# PIEFoundry_16-channel_EIB.net
KiCad netlist of a schematic drawn in EAGLE
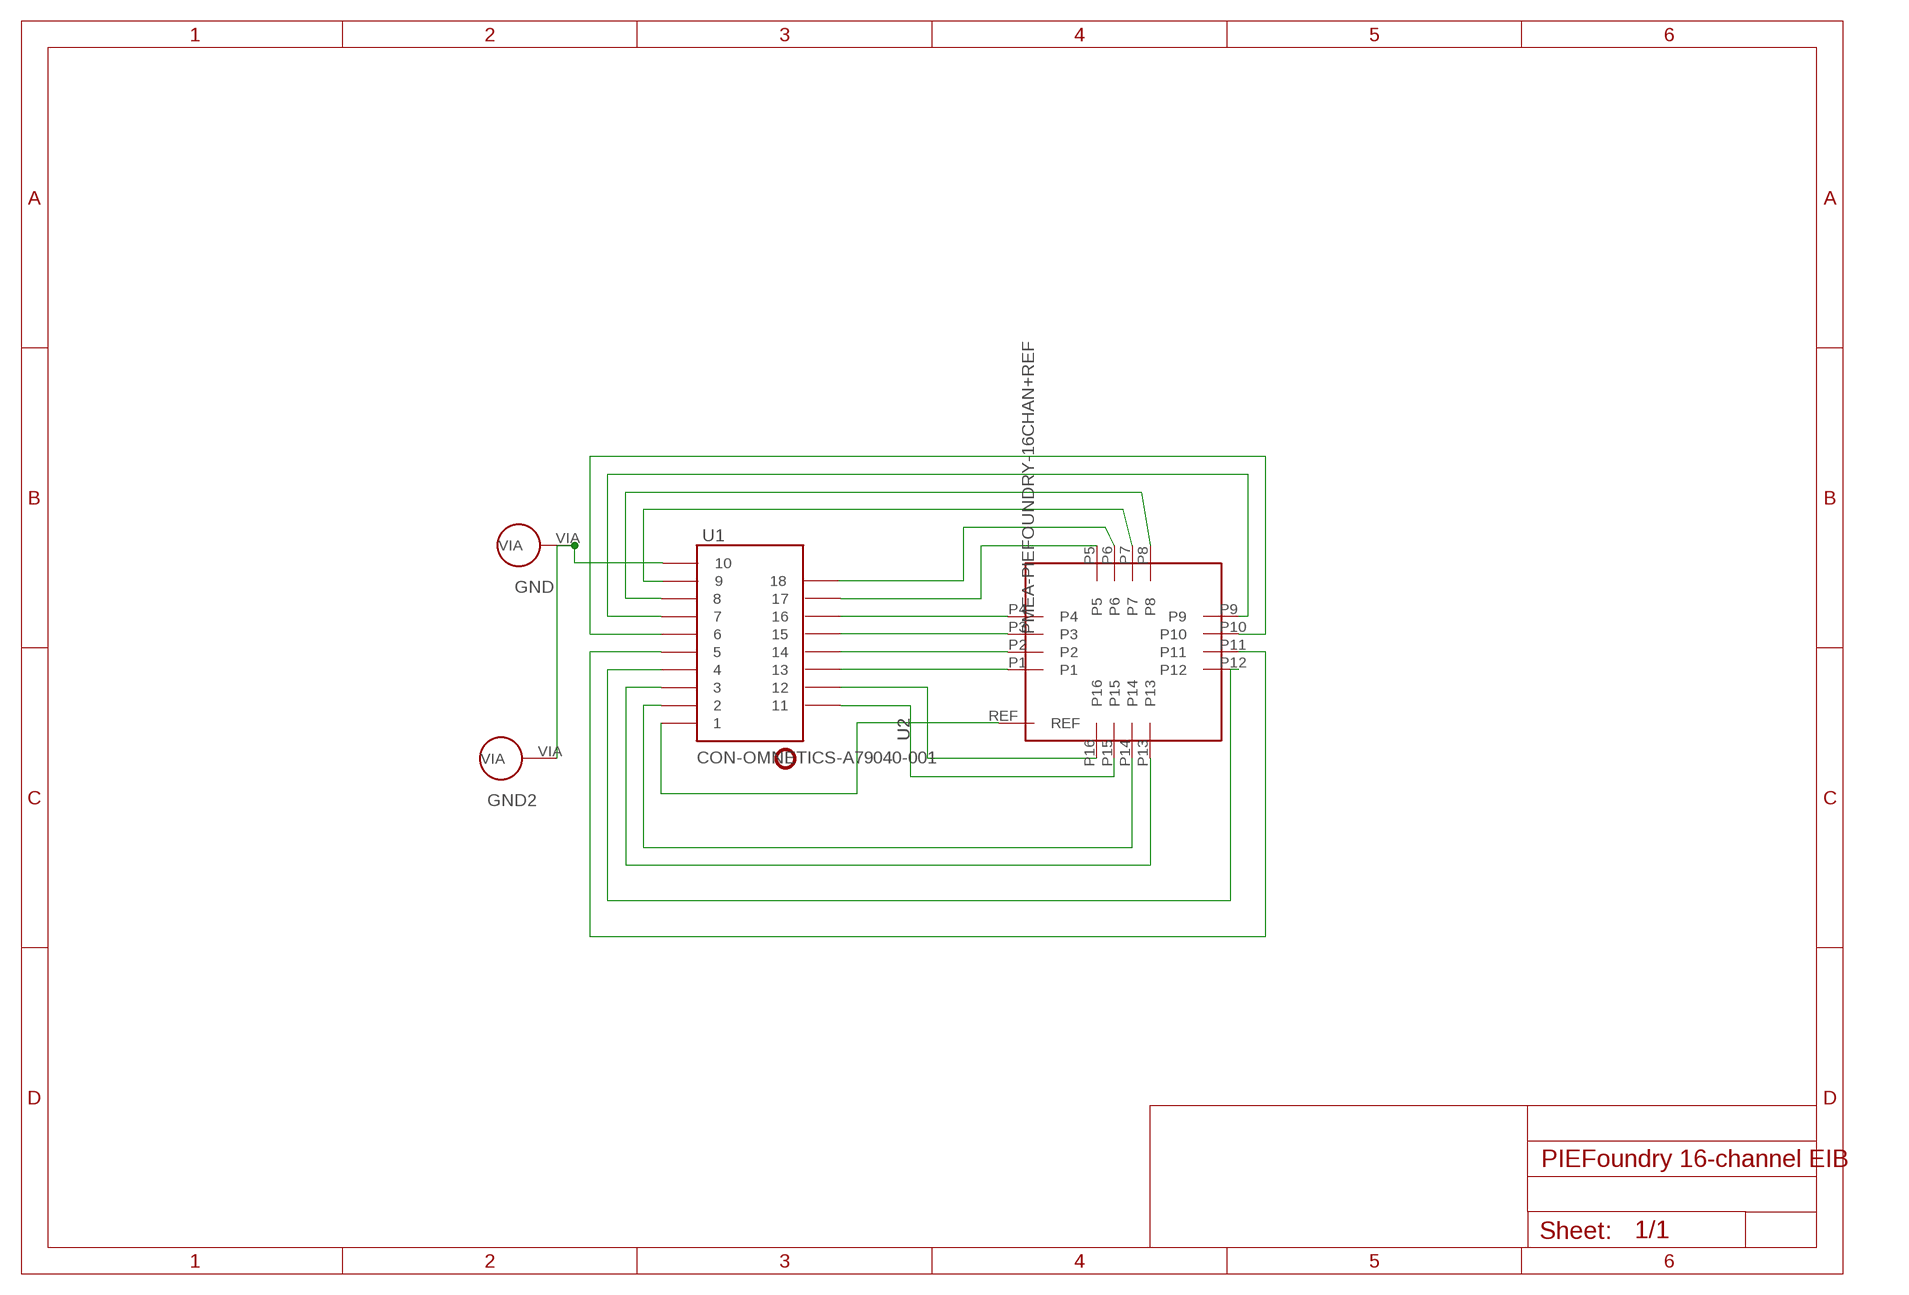
[diagram p0: schematic, sheet 1]

(export (version "E")
  (design (tool "Eeschema 10.0.6"))
  (components
    (comp (ref "GND")
      (value "SOLDER_VIA_500_UM")
      (footprint "eagle-import:SOLDER_VIA_500_UM")
      (libsource (lib "eagle-import") (part "SOLDER_VIA_500_UM"))
    )
    (comp (ref "GND2")
      (value "SOLDER_VIA_500_UM")
      (footprint "eagle-import:SOLDER_VIA_500_UM")
      (libsource (lib "eagle-import") (part "SOLDER_VIA_500_UM"))
    )
    (comp (ref "U1")
      (value "CON-OMNETICS-A79040-001")
      (footprint "eagle-import:CON-OMNETICS-A79040-001")
      (libsource (lib "eagle-import") (part "CON-OMNETICS-A79040-001"))
    )
    (comp (ref "U2")
      (value "PMEA-PIEFOUNDRY-16CHAN+REF")
      (footprint "eagle-import:PMEA-PIEFOUNDRY-16CHAN+REF")
      (libsource (lib "eagle-import") (part "PMEA-PIEFOUNDRY-16CHAN+REF"))
    )
  )
  (nets
    (net (code "1") (name "Net-(GND-PadVIA)") (class "Default")
      (node (ref "GND") (pin "VIA") (pinfunction "VIA_VIA") (pintype "bidirectional"))
      (node (ref "GND2") (pin "VIA") (pinfunction "VIA_VIA") (pintype "bidirectional"))
      (node (ref "U1") (pin "10") (pinfunction "10_10") (pintype "bidirectional"))
    )
    (net (code "2") (name "Net-(U1-Pad1)") (class "Default")
      (node (ref "U1") (pin "1") (pinfunction "1_1") (pintype "bidirectional"))
      (node (ref "U2") (pin "REF") (pinfunction "REF_REF") (pintype "bidirectional"))
    )
    (net (code "3") (name "Net-(U1-Pad2)") (class "Default")
      (node (ref "U1") (pin "2") (pinfunction "2_2") (pintype "bidirectional"))
      (node (ref "U2") (pin "P14") (pinfunction "P14_P14") (pintype "bidirectional"))
    )
    (net (code "4") (name "Net-(U1-Pad3)") (class "Default")
      (node (ref "U1") (pin "3") (pinfunction "3_3") (pintype "bidirectional"))
      (node (ref "U2") (pin "P13") (pinfunction "P13_P13") (pintype "bidirectional"))
    )
    (net (code "5") (name "Net-(U1-Pad4)") (class "Default")
      (node (ref "U1") (pin "4") (pinfunction "4_4") (pintype "bidirectional"))
      (node (ref "U2") (pin "P12") (pinfunction "P12_P12") (pintype "bidirectional"))
    )
    (net (code "6") (name "Net-(U1-Pad5)") (class "Default")
      (node (ref "U1") (pin "5") (pinfunction "5_5") (pintype "bidirectional"))
      (node (ref "U2") (pin "P11") (pinfunction "P11_P11") (pintype "bidirectional"))
    )
    (net (code "7") (name "Net-(U1-Pad6)") (class "Default")
      (node (ref "U1") (pin "6") (pinfunction "6_6") (pintype "bidirectional"))
      (node (ref "U2") (pin "P10") (pinfunction "P10_P10") (pintype "bidirectional"))
    )
    (net (code "8") (name "Net-(U1-Pad7)") (class "Default")
      (node (ref "U1") (pin "7") (pinfunction "7_7") (pintype "bidirectional"))
      (node (ref "U2") (pin "P9") (pinfunction "P9_P9") (pintype "bidirectional"))
    )
    (net (code "9") (name "Net-(U1-Pad8)") (class "Default")
      (node (ref "U1") (pin "8") (pinfunction "8_8") (pintype "bidirectional"))
      (node (ref "U2") (pin "P8") (pinfunction "P8_P8") (pintype "bidirectional"))
    )
    (net (code "10") (name "Net-(U1-Pad9)") (class "Default")
      (node (ref "U1") (pin "9") (pinfunction "9_9") (pintype "bidirectional"))
      (node (ref "U2") (pin "P7") (pinfunction "P7_P7") (pintype "bidirectional"))
    )
    (net (code "11") (name "Net-(U1-Pad11)") (class "Default")
      (node (ref "U1") (pin "11") (pinfunction "11_11") (pintype "bidirectional"))
      (node (ref "U2") (pin "P15") (pinfunction "P15_P15") (pintype "bidirectional"))
    )
    (net (code "12") (name "Net-(U1-Pad12)") (class "Default")
      (node (ref "U1") (pin "12") (pinfunction "12_12") (pintype "bidirectional"))
      (node (ref "U2") (pin "P16") (pinfunction "P16_P16") (pintype "bidirectional"))
    )
    (net (code "13") (name "Net-(U1-Pad13)") (class "Default")
      (node (ref "U1") (pin "13") (pinfunction "13_13") (pintype "bidirectional"))
      (node (ref "U2") (pin "P1") (pinfunction "P1_P1") (pintype "bidirectional"))
    )
    (net (code "14") (name "Net-(U1-Pad14)") (class "Default")
      (node (ref "U1") (pin "14") (pinfunction "14_14") (pintype "bidirectional"))
      (node (ref "U2") (pin "P2") (pinfunction "P2_P2") (pintype "bidirectional"))
    )
    (net (code "15") (name "Net-(U1-Pad15)") (class "Default")
      (node (ref "U1") (pin "15") (pinfunction "15_15") (pintype "bidirectional"))
      (node (ref "U2") (pin "P3") (pinfunction "P3_P3") (pintype "bidirectional"))
    )
    (net (code "16") (name "Net-(U1-Pad16)") (class "Default")
      (node (ref "U1") (pin "16") (pinfunction "16_16") (pintype "bidirectional"))
      (node (ref "U2") (pin "P4") (pinfunction "P4_P4") (pintype "bidirectional"))
    )
    (net (code "17") (name "Net-(U1-Pad17)") (class "Default")
      (node (ref "U1") (pin "17") (pinfunction "17_17") (pintype "bidirectional"))
      (node (ref "U2") (pin "P5") (pinfunction "P5_P5") (pintype "bidirectional"))
    )
    (net (code "18") (name "Net-(U1-Pad18)") (class "Default")
      (node (ref "U1") (pin "18") (pinfunction "18_18") (pintype "bidirectional"))
      (node (ref "U2") (pin "P6") (pinfunction "P6_P6") (pintype "bidirectional"))
    )
  )
)
